# tes1.net
KiCad netlist of a schematic drawn in EAGLE
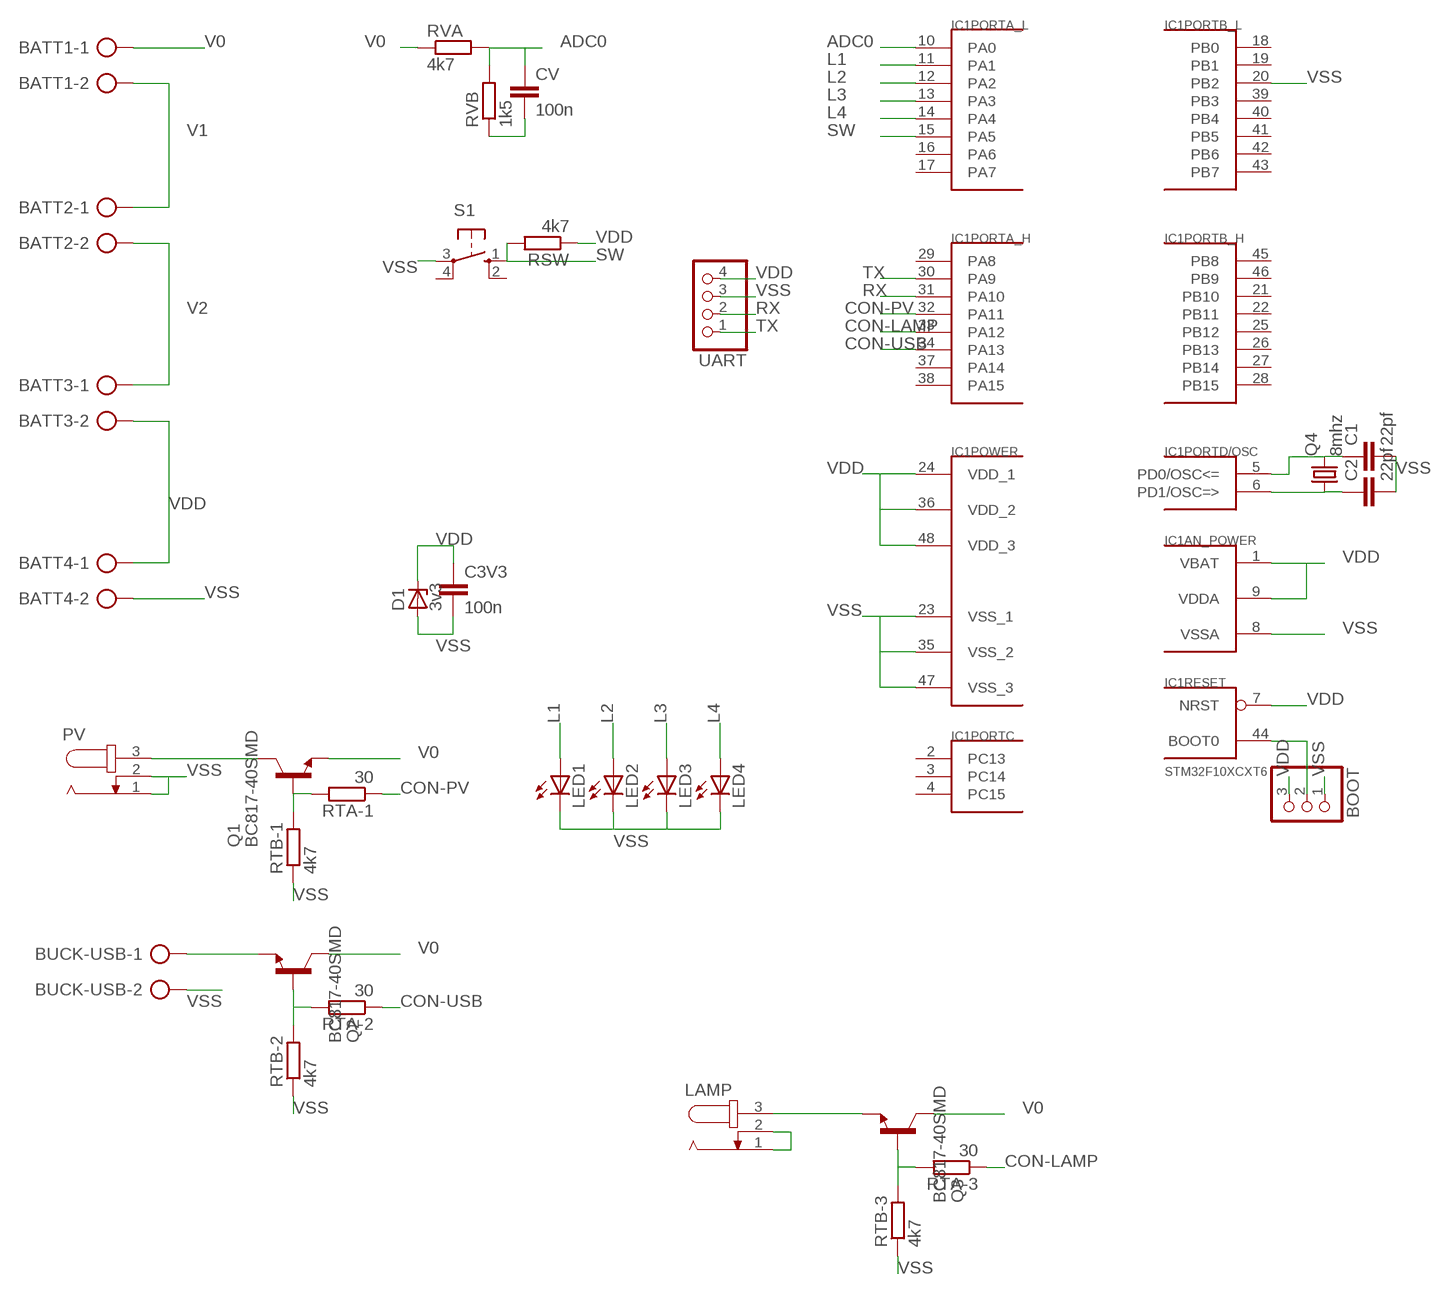
[diagram p0: schematic, sheet 1]

(export (version "E")
  (design (tool "Eeschema 10.0.6"))
  (components
    (comp (ref "BATT1")
      (value "AK300/2")
      (footprint "eagle-import:AK300_2")
      (libsource (lib "eagle-import") (part "AK300/2"))
    )
    (comp (ref "BATT2")
      (value "AK300/2")
      (footprint "eagle-import:AK300_2")
      (libsource (lib "eagle-import") (part "AK300/2"))
    )
    (comp (ref "BATT3")
      (value "AK300/2")
      (footprint "eagle-import:AK300_2")
      (libsource (lib "eagle-import") (part "AK300/2"))
    )
    (comp (ref "BATT4")
      (value "AK300/2")
      (footprint "eagle-import:AK300_2")
      (libsource (lib "eagle-import") (part "AK300/2"))
    )
    (comp (ref "BOOT")
      (value "PINHD-1X3")
      (footprint "eagle-import:1X03")
      (libsource (lib "eagle-import") (part "PINHD-1X3"))
    )
    (comp (ref "BUCK-USB")
      (value "AK300/2")
      (footprint "eagle-import:AK300_2")
      (libsource (lib "eagle-import") (part "AK300/2"))
    )
    (comp (ref "C1")
      (value "22pf")
      (footprint "eagle-import:C0805")
      (libsource (lib "eagle-import") (part "C-EUC0805"))
    )
    (comp (ref "C2")
      (value "22pf")
      (footprint "eagle-import:C0805")
      (libsource (lib "eagle-import") (part "C-EUC0805"))
    )
    (comp (ref "C3V3")
      (value "100n")
      (footprint "eagle-import:C0805")
      (libsource (lib "eagle-import") (part "C-EUC0805"))
    )
    (comp (ref "CV")
      (value "100n")
      (footprint "eagle-import:C0805")
      (libsource (lib "eagle-import") (part "C-EUC0805"))
    )
    (comp (ref "D1")
      (value "3v3")
      (footprint "eagle-import:SMB")
      (libsource (lib "eagle-import") (part "ZENER-DIODESMB"))
    )
    (comp (ref "IC1")
      (value "STM32F10XCXT6")
      (footprint "eagle-import:TQFP48")
      (libsource (lib "eagle-import") (part "STM32F10XCXT6"))
    )
    (comp (ref "LAMP")
      (value "JACK-PLUG0")
      (footprint "eagle-import:SPC4077")
      (libsource (lib "eagle-import") (part "JACK-PLUG0"))
    )
    (comp (ref "LED1")
      (value "LEDCHIP-LED0805")
      (footprint "eagle-import:CHIP-LED0805")
      (libsource (lib "eagle-import") (part "LEDCHIP-LED0805"))
    )
    (comp (ref "LED2")
      (value "LEDCHIP-LED0805")
      (footprint "eagle-import:CHIP-LED0805")
      (libsource (lib "eagle-import") (part "LEDCHIP-LED0805"))
    )
    (comp (ref "LED3")
      (value "LEDCHIP-LED0805")
      (footprint "eagle-import:CHIP-LED0805")
      (libsource (lib "eagle-import") (part "LEDCHIP-LED0805"))
    )
    (comp (ref "LED4")
      (value "LEDCHIP-LED0805")
      (footprint "eagle-import:CHIP-LED0805")
      (libsource (lib "eagle-import") (part "LEDCHIP-LED0805"))
    )
    (comp (ref "PV")
      (value "JACK-PLUG0")
      (footprint "eagle-import:SPC4077")
      (libsource (lib "eagle-import") (part "JACK-PLUG0"))
    )
    (comp (ref "Q1")
      (value "BC817-40SMD")
      (footprint "eagle-import:SOT23-BEC")
      (libsource (lib "eagle-import") (part "BC817SMD-40"))
    )
    (comp (ref "Q2")
      (value "BC817-40SMD")
      (footprint "eagle-import:SOT23-BEC")
      (libsource (lib "eagle-import") (part "BC817SMD-40"))
    )
    (comp (ref "Q3")
      (value "BC817-40SMD")
      (footprint "eagle-import:SOT23-BEC")
      (libsource (lib "eagle-import") (part "BC817SMD-40"))
    )
    (comp (ref "Q4")
      (value "8mhz")
      (footprint "eagle-import:HC49U-V")
      (libsource (lib "eagle-import") (part "CRYSTALHC49U-V"))
    )
    (comp (ref "RSW")
      (value "4k7")
      (footprint "eagle-import:R0805")
      (libsource (lib "eagle-import") (part "R-EU_R0805"))
    )
    (comp (ref "RTA-1")
      (value "30")
      (footprint "eagle-import:R0805")
      (libsource (lib "eagle-import") (part "R-EU_R0805"))
    )
    (comp (ref "RTA-2")
      (value "30")
      (footprint "eagle-import:R0805")
      (libsource (lib "eagle-import") (part "R-EU_R0805"))
    )
    (comp (ref "RTA-3")
      (value "30")
      (footprint "eagle-import:R0805")
      (libsource (lib "eagle-import") (part "R-EU_R0805"))
    )
    (comp (ref "RTB-1")
      (value "4k7")
      (footprint "eagle-import:R0805")
      (libsource (lib "eagle-import") (part "R-EU_R0805"))
    )
    (comp (ref "RTB-2")
      (value "4k7")
      (footprint "eagle-import:R0805")
      (libsource (lib "eagle-import") (part "R-EU_R0805"))
    )
    (comp (ref "RTB-3")
      (value "4k7")
      (footprint "eagle-import:R0805")
      (libsource (lib "eagle-import") (part "R-EU_R0805"))
    )
    (comp (ref "RVA")
      (value "4k7")
      (footprint "eagle-import:R0805")
      (libsource (lib "eagle-import") (part "R-EU_R0805"))
    )
    (comp (ref "RVB")
      (value "1k5")
      (footprint "eagle-import:R0805")
      (libsource (lib "eagle-import") (part "R-EU_R0805"))
    )
    (comp (ref "S1")
      (value "10-XX")
      (footprint "eagle-import:B3F-10XX")
      (fields (field (name "MPN") "B3F-1000"))
      (libsource (lib "eagle-import") (part "10-XX"))
    )
    (comp (ref "UART")
      (value "PINHD-1X4")
      (footprint "eagle-import:1X04")
      (libsource (lib "eagle-import") (part "PINHD-1X4"))
    )
  )
  (nets
    (net (code "1") (name "/ADC0") (class "Default")
      (node (ref "CV") (pin "1") (pinfunction "1_1") (pintype "passive"))
      (node (ref "IC1") (pin "10") (pinfunction "PA0_10") (pintype "bidirectional"))
      (node (ref "RVA") (pin "2") (pinfunction "2_2") (pintype "passive"))
      (node (ref "RVB") (pin "2") (pinfunction "2_2") (pintype "passive"))
    )
    (net (code "2") (name "/CON-LAMP") (class "Default")
      (node (ref "IC1") (pin "33") (pinfunction "PA12_33") (pintype "bidirectional"))
      (node (ref "RTA-3") (pin "1") (pinfunction "1_1") (pintype "passive"))
    )
    (net (code "3") (name "/CON-PV") (class "Default")
      (node (ref "IC1") (pin "32") (pinfunction "PA11_32") (pintype "bidirectional"))
      (node (ref "RTA-1") (pin "1") (pinfunction "1_1") (pintype "passive"))
    )
    (net (code "4") (name "/CON-USB") (class "Default")
      (node (ref "IC1") (pin "34") (pinfunction "PA13_34") (pintype "bidirectional"))
      (node (ref "RTA-2") (pin "1") (pinfunction "1_1") (pintype "passive"))
    )
    (net (code "5") (name "/L1") (class "Default")
      (node (ref "IC1") (pin "11") (pinfunction "PA1_11") (pintype "bidirectional"))
      (node (ref "LED1") (pin "A") (pinfunction "A_A") (pintype "passive"))
    )
    (net (code "6") (name "/L2") (class "Default")
      (node (ref "IC1") (pin "12") (pinfunction "PA2_12") (pintype "bidirectional"))
      (node (ref "LED2") (pin "A") (pinfunction "A_A") (pintype "passive"))
    )
    (net (code "7") (name "/L3") (class "Default")
      (node (ref "IC1") (pin "13") (pinfunction "PA3_13") (pintype "bidirectional"))
      (node (ref "LED3") (pin "A") (pinfunction "A_A") (pintype "passive"))
    )
    (net (code "8") (name "/L4") (class "Default")
      (node (ref "IC1") (pin "14") (pinfunction "PA4_14") (pintype "bidirectional"))
      (node (ref "LED4") (pin "A") (pinfunction "A_A") (pintype "passive"))
    )
    (net (code "9") (name "/RX") (class "Default")
      (node (ref "IC1") (pin "31") (pinfunction "PA10_31") (pintype "bidirectional"))
      (node (ref "UART") (pin "2") (pinfunction "2_2") (pintype "passive"))
    )
    (net (code "10") (name "/SW") (class "Default")
      (node (ref "IC1") (pin "15") (pinfunction "PA5_15") (pintype "bidirectional"))
      (node (ref "RSW") (pin "2") (pinfunction "2_2") (pintype "passive"))
      (node (ref "S1") (pin "1") (pinfunction "S_1") (pintype "passive"))
    )
    (net (code "11") (name "/TX") (class "Default")
      (node (ref "IC1") (pin "30") (pinfunction "PA9_30") (pintype "bidirectional"))
      (node (ref "UART") (pin "1") (pinfunction "1_1") (pintype "passive"))
    )
    (net (code "12") (name "/V0") (class "Default")
      (node (ref "BATT1") (pin "1") (pinfunction "KL_1") (pintype "passive"))
      (node (ref "Q1") (pin "E") (pinfunction "E_E") (pintype "passive"))
      (node (ref "Q2") (pin "C") (pinfunction "C_C") (pintype "passive"))
      (node (ref "Q3") (pin "C") (pinfunction "C_C") (pintype "passive"))
      (node (ref "RVA") (pin "1") (pinfunction "1_1") (pintype "passive"))
    )
    (net (code "13") (name "/V1") (class "Default")
      (node (ref "BATT1") (pin "2") (pinfunction "KL_2") (pintype "passive"))
      (node (ref "BATT2") (pin "1") (pinfunction "KL_1") (pintype "passive"))
    )
    (net (code "14") (name "/V2") (class "Default")
      (node (ref "BATT2") (pin "2") (pinfunction "KL_2") (pintype "passive"))
      (node (ref "BATT3") (pin "1") (pinfunction "KL_1") (pintype "passive"))
    )
    (net (code "15") (name "/VDD") (class "Default")
      (node (ref "BATT3") (pin "2") (pinfunction "KL_2") (pintype "passive"))
      (node (ref "BATT4") (pin "1") (pinfunction "KL_1") (pintype "passive"))
      (node (ref "BOOT") (pin "3") (pinfunction "3_3") (pintype "passive"))
      (node (ref "C3V3") (pin "1") (pinfunction "1_1") (pintype "passive"))
      (node (ref "D1") (pin "C") (pinfunction "C_C") (pintype "passive"))
      (node (ref "IC1") (pin "1") (pinfunction "VBAT_1") (pintype "power_in"))
      (node (ref "IC1") (pin "24") (pinfunction "VDD_1_24") (pintype "power_in"))
      (node (ref "IC1") (pin "36") (pinfunction "VDD_2_36") (pintype "power_in"))
      (node (ref "IC1") (pin "48") (pinfunction "VDD_3_48") (pintype "power_in"))
      (node (ref "IC1") (pin "7") (pinfunction "NRST_7") (pintype "input"))
      (node (ref "IC1") (pin "9") (pinfunction "VDDA_9") (pintype "power_in"))
      (node (ref "RSW") (pin "1") (pinfunction "1_1") (pintype "passive"))
      (node (ref "UART") (pin "4") (pinfunction "4_4") (pintype "passive"))
    )
    (net (code "16") (name "/VSS") (class "Default")
      (node (ref "BATT4") (pin "2") (pinfunction "KL_2") (pintype "passive"))
      (node (ref "BOOT") (pin "1") (pinfunction "1_1") (pintype "passive"))
      (node (ref "BUCK-USB") (pin "2") (pinfunction "KL_2") (pintype "passive"))
      (node (ref "C1") (pin "2") (pinfunction "2_2") (pintype "passive"))
      (node (ref "C2") (pin "2") (pinfunction "2_2") (pintype "passive"))
      (node (ref "C3V3") (pin "2") (pinfunction "2_2") (pintype "passive"))
      (node (ref "CV") (pin "2") (pinfunction "2_2") (pintype "passive"))
      (node (ref "D1") (pin "A") (pinfunction "A_A") (pintype "passive"))
      (node (ref "IC1") (pin "20") (pinfunction "PB2_20") (pintype "bidirectional"))
      (node (ref "IC1") (pin "23") (pinfunction "VSS_1_23") (pintype "power_in"))
      (node (ref "IC1") (pin "35") (pinfunction "VSS_2_35") (pintype "power_in"))
      (node (ref "IC1") (pin "47") (pinfunction "VSS_3_47") (pintype "power_in"))
      (node (ref "IC1") (pin "8") (pinfunction "VSSA_8") (pintype "power_in"))
      (node (ref "LAMP") (pin "1") (pinfunction "1_1") (pintype "passive"))
      (node (ref "LAMP") (pin "2") (pinfunction "2_2") (pintype "passive"))
      (node (ref "LED1") (pin "C") (pinfunction "C_C") (pintype "passive"))
      (node (ref "LED2") (pin "C") (pinfunction "C_C") (pintype "passive"))
      (node (ref "LED3") (pin "C") (pinfunction "C_C") (pintype "passive"))
      (node (ref "LED4") (pin "C") (pinfunction "C_C") (pintype "passive"))
      (node (ref "PV") (pin "1") (pinfunction "1_1") (pintype "passive"))
      (node (ref "PV") (pin "2") (pinfunction "2_2") (pintype "passive"))
      (node (ref "RTB-1") (pin "1") (pinfunction "1_1") (pintype "passive"))
      (node (ref "RTB-2") (pin "1") (pinfunction "1_1") (pintype "passive"))
      (node (ref "RTB-3") (pin "1") (pinfunction "1_1") (pintype "passive"))
      (node (ref "RVB") (pin "1") (pinfunction "1_1") (pintype "passive"))
      (node (ref "S1") (pin "3") (pinfunction "P_3") (pintype "passive"))
      (node (ref "UART") (pin "3") (pinfunction "3_3") (pintype "passive"))
    )
    (net (code "17") (name "Net-(BUCK-USBA-KL)") (class "Default")
      (node (ref "BUCK-USB") (pin "1") (pinfunction "KL_1") (pintype "passive"))
      (node (ref "Q2") (pin "E") (pinfunction "E_E") (pintype "passive"))
    )
    (net (code "18") (name "Net-(IC1G-PD0{slash}OSC<=)") (class "Default")
      (node (ref "C1") (pin "1") (pinfunction "1_1") (pintype "passive"))
      (node (ref "IC1") (pin "5") (pinfunction "PD0/OSC<=_5") (pintype "bidirectional"))
      (node (ref "Q4") (pin "2") (pinfunction "2_2") (pintype "passive"))
    )
    (net (code "19") (name "Net-(IC1G-PD1{slash}OSC=>)") (class "Default")
      (node (ref "C2") (pin "1") (pinfunction "1_1") (pintype "passive"))
      (node (ref "IC1") (pin "6") (pinfunction "PD1/OSC=>_6") (pintype "bidirectional"))
      (node (ref "Q4") (pin "1") (pinfunction "1_1") (pintype "passive"))
    )
    (net (code "20") (name "Net-(IC1I-BOOT0)") (class "Default")
      (node (ref "BOOT") (pin "2") (pinfunction "2_2") (pintype "passive"))
      (node (ref "IC1") (pin "44") (pinfunction "BOOT0_44") (pintype "input"))
    )
    (net (code "21") (name "Net-(LAMP-Pad3)") (class "Default")
      (node (ref "LAMP") (pin "3") (pinfunction "3_3") (pintype "passive"))
      (node (ref "Q3") (pin "E") (pinfunction "E_E") (pintype "passive"))
    )
    (net (code "22") (name "Net-(PV-Pad3)") (class "Default")
      (node (ref "PV") (pin "3") (pinfunction "3_3") (pintype "passive"))
      (node (ref "Q1") (pin "C") (pinfunction "C_C") (pintype "passive"))
    )
    (net (code "23") (name "Net-(Q1-PadB)") (class "Default")
      (node (ref "Q1") (pin "B") (pinfunction "B_B") (pintype "passive"))
      (node (ref "RTA-1") (pin "2") (pinfunction "2_2") (pintype "passive"))
      (node (ref "RTB-1") (pin "2") (pinfunction "2_2") (pintype "passive"))
    )
    (net (code "24") (name "Net-(Q2-PadB)") (class "Default")
      (node (ref "Q2") (pin "B") (pinfunction "B_B") (pintype "passive"))
      (node (ref "RTA-2") (pin "2") (pinfunction "2_2") (pintype "passive"))
      (node (ref "RTB-2") (pin "2") (pinfunction "2_2") (pintype "passive"))
    )
    (net (code "25") (name "Net-(Q3-PadB)") (class "Default")
      (node (ref "Q3") (pin "B") (pinfunction "B_B") (pintype "passive"))
      (node (ref "RTA-3") (pin "2") (pinfunction "2_2") (pintype "passive"))
      (node (ref "RTB-3") (pin "2") (pinfunction "2_2") (pintype "passive"))
    )
    (net (code "26") (name "unconnected-(IC1B-PA8-Pad29)") (class "Default")
      (node (ref "IC1") (pin "29") (pinfunction "PA8_29") (pintype "bidirectional"))
    )
    (net (code "27") (name "unconnected-(IC1B-PA14-Pad37)") (class "Default")
      (node (ref "IC1") (pin "37") (pinfunction "PA14_37") (pintype "bidirectional"))
    )
    (net (code "28") (name "unconnected-(IC1B-PA15-Pad38)") (class "Default")
      (node (ref "IC1") (pin "38") (pinfunction "PA15_38") (pintype "bidirectional"))
    )
    (net (code "29") (name "unconnected-(IC1C-PA6-Pad16)") (class "Default")
      (node (ref "IC1") (pin "16") (pinfunction "PA6_16") (pintype "bidirectional"))
    )
    (net (code "30") (name "unconnected-(IC1C-PA7-Pad17)") (class "Default")
      (node (ref "IC1") (pin "17") (pinfunction "PA7_17") (pintype "bidirectional"))
    )
    (net (code "31") (name "unconnected-(IC1D-PB8-Pad45)") (class "Default")
      (node (ref "IC1") (pin "45") (pinfunction "PB8_45") (pintype "bidirectional"))
    )
    (net (code "32") (name "unconnected-(IC1D-PB9-Pad46)") (class "Default")
      (node (ref "IC1") (pin "46") (pinfunction "PB9_46") (pintype "bidirectional"))
    )
    (net (code "33") (name "unconnected-(IC1D-PB10-Pad21)") (class "Default")
      (node (ref "IC1") (pin "21") (pinfunction "PB10_21") (pintype "bidirectional"))
    )
    (net (code "34") (name "unconnected-(IC1D-PB11-Pad22)") (class "Default")
      (node (ref "IC1") (pin "22") (pinfunction "PB11_22") (pintype "bidirectional"))
    )
    (net (code "35") (name "unconnected-(IC1D-PB12-Pad25)") (class "Default")
      (node (ref "IC1") (pin "25") (pinfunction "PB12_25") (pintype "bidirectional"))
    )
    (net (code "36") (name "unconnected-(IC1D-PB13-Pad26)") (class "Default")
      (node (ref "IC1") (pin "26") (pinfunction "PB13_26") (pintype "bidirectional"))
    )
    (net (code "37") (name "unconnected-(IC1D-PB14-Pad27)") (class "Default")
      (node (ref "IC1") (pin "27") (pinfunction "PB14_27") (pintype "bidirectional"))
    )
    (net (code "38") (name "unconnected-(IC1D-PB15-Pad28)") (class "Default")
      (node (ref "IC1") (pin "28") (pinfunction "PB15_28") (pintype "bidirectional"))
    )
    (net (code "39") (name "unconnected-(IC1E-PB0-Pad18)") (class "Default")
      (node (ref "IC1") (pin "18") (pinfunction "PB0_18") (pintype "bidirectional"))
    )
    (net (code "40") (name "unconnected-(IC1E-PB1-Pad19)") (class "Default")
      (node (ref "IC1") (pin "19") (pinfunction "PB1_19") (pintype "bidirectional"))
    )
    (net (code "41") (name "unconnected-(IC1E-PB3-Pad39)") (class "Default")
      (node (ref "IC1") (pin "39") (pinfunction "PB3_39") (pintype "bidirectional"))
    )
    (net (code "42") (name "unconnected-(IC1E-PB4-Pad40)") (class "Default")
      (node (ref "IC1") (pin "40") (pinfunction "PB4_40") (pintype "bidirectional"))
    )
    (net (code "43") (name "unconnected-(IC1E-PB5-Pad41)") (class "Default")
      (node (ref "IC1") (pin "41") (pinfunction "PB5_41") (pintype "bidirectional"))
    )
    (net (code "44") (name "unconnected-(IC1E-PB6-Pad42)") (class "Default")
      (node (ref "IC1") (pin "42") (pinfunction "PB6_42") (pintype "bidirectional"))
    )
    (net (code "45") (name "unconnected-(IC1E-PB7-Pad43)") (class "Default")
      (node (ref "IC1") (pin "43") (pinfunction "PB7_43") (pintype "bidirectional"))
    )
    (net (code "46") (name "unconnected-(IC1F-PC13-Pad2)") (class "Default")
      (node (ref "IC1") (pin "2") (pinfunction "PC13_2") (pintype "bidirectional"))
    )
    (net (code "47") (name "unconnected-(IC1F-PC14-Pad3)") (class "Default")
      (node (ref "IC1") (pin "3") (pinfunction "PC14_3") (pintype "bidirectional"))
    )
    (net (code "48") (name "unconnected-(IC1F-PC15-Pad4)") (class "Default")
      (node (ref "IC1") (pin "4") (pinfunction "PC15_4") (pintype "bidirectional"))
    )
    (net (code "49") (name "unconnected-(S1-P1-Pad4)") (class "Default")
      (node (ref "S1") (pin "4") (pinfunction "P1_4") (pintype "passive"))
    )
    (net (code "50") (name "unconnected-(S1-S1-Pad2)") (class "Default")
      (node (ref "S1") (pin "2") (pinfunction "S1_2") (pintype "passive"))
    )
  )
)
